# WaeatherNode.net
KiCad netlist of a schematic drawn in EAGLE
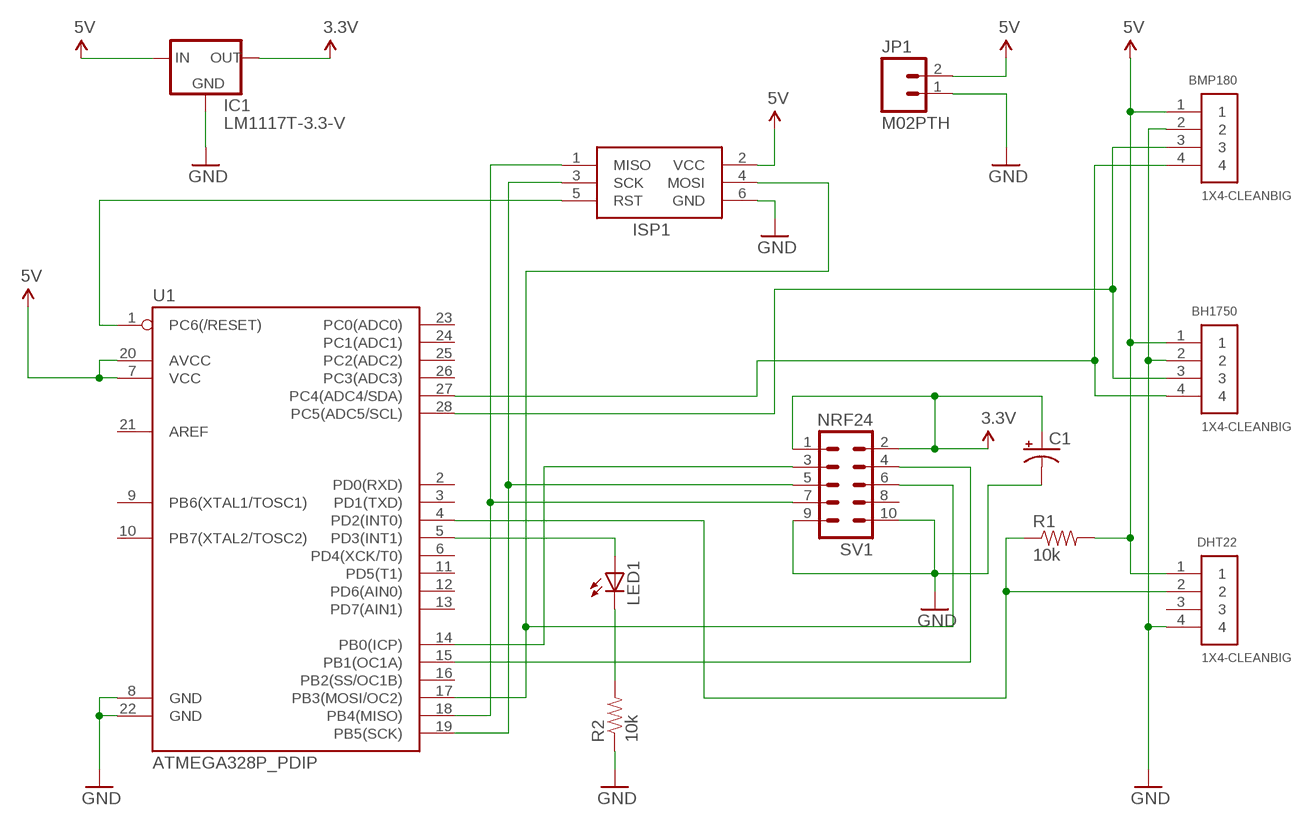
[diagram p0: schematic, sheet 1]

(export (version "E")
  (design (tool "Eeschema 10.0.6"))
  (components
    (comp (ref "BH1750")
      (value "1X4-CLEANBIG")
      (footprint "eagle-import:1X04-CLEANBIG")
      (libsource (lib "eagle-import") (part "1X4-CLEANBIG"))
    )
    (comp (ref "BMP180")
      (value "1X4-CLEANBIG")
      (footprint "eagle-import:1X04-CLEANBIG")
      (libsource (lib "eagle-import") (part "1X4-CLEANBIG"))
    )
    (comp (ref "C1")
      (value "CPOL-USE2.5-7")
      (footprint "eagle-import:E2,5-7")
      (libsource (lib "eagle-import") (part "CPOL-USE2.5-7"))
    )
    (comp (ref "DHT22")
      (value "1X4-CLEANBIG")
      (footprint "eagle-import:1X04-CLEANBIG")
      (libsource (lib "eagle-import") (part "1X4-CLEANBIG"))
    )
    (comp (ref "IC1")
      (value "LM1117T-3.3-V")
      (footprint "eagle-import:TO220V")
      (libsource (lib "eagle-import") (part "LM1117T--V3.3"))
    )
    (comp (ref "ISP1")
      (value "AVRISP-BOX")
      (footprint "eagle-import:AVRISP-BOX")
      (libsource (lib "eagle-import") (part "AVRISP-BOX"))
    )
    (comp (ref "JP1")
      (value "M02PTH")
      (footprint "eagle-import:1X02")
      (libsource (lib "eagle-import") (part "M02PTH"))
    )
    (comp (ref "LED1")
      (value "LED3MM")
      (footprint "eagle-import:LED3MM")
      (libsource (lib "eagle-import") (part "LED3MM"))
    )
    (comp (ref "R1")
      (value "10k")
      (footprint "eagle-import:AXIAL-0.3")
      (libsource (lib "eagle-import") (part "10KOHM-1/4W-1%(PTH)HORIZ"))
    )
    (comp (ref "R2")
      (value "10k")
      (footprint "eagle-import:AXIAL-0.3")
      (libsource (lib "eagle-import") (part "10KOHM-1/4W-1%(PTH)HORIZ"))
    )
    (comp (ref "SV1")
      (value "NRF24")
      (footprint "eagle-import:MA05-2")
      (libsource (lib "eagle-import") (part "MA05-2"))
    )
    (comp (ref "U1")
      (value "ATMEGA328P_PDIP")
      (footprint "eagle-import:DIL28-3")
      (libsource (lib "eagle-import") (part "ATMEGA328P_PDIP"))
    )
  )
  (nets
    (net (code "1") (name "3.3V") (class "Default")
      (node (ref "C1") (pin "+") (pinfunction "+_+") (pintype "passive"))
      (node (ref "IC1") (pin "2") (pinfunction "OUT_2") (pintype "passive"))
      (node (ref "SV1") (pin "1") (pinfunction "1_1") (pintype "passive"))
      (node (ref "SV1") (pin "2") (pinfunction "2_2") (pintype "passive"))
    )
    (net (code "2") (name "5V") (class "Default")
      (node (ref "BH1750") (pin "1") (pinfunction "1_1") (pintype "bidirectional"))
      (node (ref "BMP180") (pin "1") (pinfunction "1_1") (pintype "bidirectional"))
      (node (ref "DHT22") (pin "1") (pinfunction "1_1") (pintype "bidirectional"))
      (node (ref "IC1") (pin "3") (pinfunction "IN_3") (pintype "input"))
      (node (ref "ISP1") (pin "2") (pinfunction "VCC_2") (pintype "power_in"))
      (node (ref "JP1") (pin "2") (pinfunction "2_2") (pintype "passive"))
      (node (ref "R1") (pin "P$2") (pinfunction "2_P$2") (pintype "passive"))
      (node (ref "U1") (pin "20") (pinfunction "AVCC_20") (pintype "bidirectional"))
      (node (ref "U1") (pin "7") (pinfunction "VCC_7") (pintype "bidirectional"))
    )
    (net (code "3") (name "GND") (class "Default")
      (node (ref "BH1750") (pin "2") (pinfunction "2_2") (pintype "bidirectional"))
      (node (ref "BMP180") (pin "2") (pinfunction "2_2") (pintype "bidirectional"))
      (node (ref "C1") (pin "-") (pinfunction "-_-") (pintype "passive"))
      (node (ref "DHT22") (pin "4") (pinfunction "4_4") (pintype "bidirectional"))
      (node (ref "IC1") (pin "1") (pinfunction "GND_1") (pintype "input"))
      (node (ref "ISP1") (pin "6") (pinfunction "GND_6") (pintype "power_in"))
      (node (ref "JP1") (pin "1") (pinfunction "1_1") (pintype "passive"))
      (node (ref "R2") (pin "P$1") (pinfunction "1_P$1") (pintype "passive"))
      (node (ref "SV1") (pin "10") (pinfunction "10_10") (pintype "passive"))
      (node (ref "SV1") (pin "9") (pinfunction "9_9") (pintype "passive"))
      (node (ref "U1") (pin "22") (pinfunction "GND_22") (pintype "bidirectional"))
      (node (ref "U1") (pin "8") (pinfunction "GND_8") (pintype "bidirectional"))
    )
    (net (code "4") (name "Net-(ISP1-MISO)") (class "Default")
      (node (ref "ISP1") (pin "1") (pinfunction "MISO_1") (pintype "input"))
      (node (ref "SV1") (pin "7") (pinfunction "7_7") (pintype "passive"))
      (node (ref "U1") (pin "18") (pinfunction "PB4(MISO)_18") (pintype "bidirectional"))
    )
    (net (code "5") (name "Net-(ISP1-MOSI)") (class "Default")
      (node (ref "ISP1") (pin "4") (pinfunction "MOSI_4") (pintype "output"))
      (node (ref "SV1") (pin "6") (pinfunction "6_6") (pintype "passive"))
      (node (ref "U1") (pin "17") (pinfunction "PB3(MOSI/OC2)_17") (pintype "bidirectional"))
    )
    (net (code "6") (name "Net-(ISP1-RST)") (class "Default")
      (node (ref "ISP1") (pin "5") (pinfunction "RST_5") (pintype "output"))
      (node (ref "U1") (pin "1") (pinfunction "PC6(/RESET)_1") (pintype "bidirectional"))
    )
    (net (code "7") (name "Net-(ISP1-SCK)") (class "Default")
      (node (ref "ISP1") (pin "3") (pinfunction "SCK_3") (pintype "output"))
      (node (ref "SV1") (pin "5") (pinfunction "5_5") (pintype "passive"))
      (node (ref "U1") (pin "19") (pinfunction "PB5(SCK)_19") (pintype "bidirectional"))
    )
    (net (code "8") (name "Net-(LED1-C)") (class "Default")
      (node (ref "LED1") (pin "K") (pinfunction "C_K") (pintype "passive"))
      (node (ref "R2") (pin "P$2") (pinfunction "2_P$2") (pintype "passive"))
    )
    (net (code "9") (name "Net-(R1-1)") (class "Default")
      (node (ref "DHT22") (pin "2") (pinfunction "2_2") (pintype "bidirectional"))
      (node (ref "R1") (pin "P$1") (pinfunction "1_P$1") (pintype "passive"))
      (node (ref "U1") (pin "4") (pinfunction "PD2(INT0)_4") (pintype "bidirectional"))
    )
    (net (code "10") (name "Net-(U1-PB0(ICP))") (class "Default")
      (node (ref "SV1") (pin "3") (pinfunction "3_3") (pintype "passive"))
      (node (ref "U1") (pin "14") (pinfunction "PB0(ICP)_14") (pintype "bidirectional"))
    )
    (net (code "11") (name "Net-(U1-PB1(OC1A))") (class "Default")
      (node (ref "SV1") (pin "4") (pinfunction "4_4") (pintype "passive"))
      (node (ref "U1") (pin "15") (pinfunction "PB1(OC1A)_15") (pintype "bidirectional"))
    )
    (net (code "12") (name "Net-(U1-PC4(ADC4{slash}SDA))") (class "Default")
      (node (ref "BH1750") (pin "4") (pinfunction "4_4") (pintype "bidirectional"))
      (node (ref "BMP180") (pin "4") (pinfunction "4_4") (pintype "bidirectional"))
      (node (ref "U1") (pin "27") (pinfunction "PC4(ADC4/SDA)_27") (pintype "bidirectional"))
    )
    (net (code "13") (name "Net-(U1-PC5(ADC5{slash}SCL))") (class "Default")
      (node (ref "BH1750") (pin "3") (pinfunction "3_3") (pintype "bidirectional"))
      (node (ref "BMP180") (pin "3") (pinfunction "3_3") (pintype "bidirectional"))
      (node (ref "U1") (pin "28") (pinfunction "PC5(ADC5/SCL)_28") (pintype "bidirectional"))
    )
    (net (code "14") (name "Net-(U1-PD3(INT1))") (class "Default")
      (node (ref "LED1") (pin "A") (pinfunction "A_A") (pintype "passive"))
      (node (ref "U1") (pin "5") (pinfunction "PD3(INT1)_5") (pintype "bidirectional"))
    )
    (net (code "15") (name "unconnected-(DHT22-Pad3)") (class "Default")
      (node (ref "DHT22") (pin "3") (pinfunction "3_3") (pintype "bidirectional"))
    )
    (net (code "16") (name "unconnected-(SV1-Pad8)") (class "Default")
      (node (ref "SV1") (pin "8") (pinfunction "8_8") (pintype "passive"))
    )
    (net (code "17") (name "unconnected-(U1-AREF-Pad21)") (class "Default")
      (node (ref "U1") (pin "21") (pinfunction "AREF_21") (pintype "bidirectional"))
    )
    (net (code "18") (name "unconnected-(U1-PB2(SS{slash}OC1B)-Pad16)") (class "Default")
      (node (ref "U1") (pin "16") (pinfunction "PB2(SS/OC1B)_16") (pintype "bidirectional"))
    )
    (net (code "19") (name "unconnected-(U1-PB6(XTAL1{slash}TOSC1)-Pad9)") (class "Default")
      (node (ref "U1") (pin "9") (pinfunction "PB6(XTAL1/TOSC1)_9") (pintype "bidirectional"))
    )
    (net (code "20") (name "unconnected-(U1-PB7(XTAL2{slash}TOSC2)-Pad10)") (class "Default")
      (node (ref "U1") (pin "10") (pinfunction "PB7(XTAL2/TOSC2)_10") (pintype "bidirectional"))
    )
    (net (code "21") (name "unconnected-(U1-PC0(ADC0)-Pad23)") (class "Default")
      (node (ref "U1") (pin "23") (pinfunction "PC0(ADC0)_23") (pintype "bidirectional"))
    )
    (net (code "22") (name "unconnected-(U1-PC1(ADC1)-Pad24)") (class "Default")
      (node (ref "U1") (pin "24") (pinfunction "PC1(ADC1)_24") (pintype "bidirectional"))
    )
    (net (code "23") (name "unconnected-(U1-PC2(ADC2)-Pad25)") (class "Default")
      (node (ref "U1") (pin "25") (pinfunction "PC2(ADC2)_25") (pintype "bidirectional"))
    )
    (net (code "24") (name "unconnected-(U1-PC3(ADC3)-Pad26)") (class "Default")
      (node (ref "U1") (pin "26") (pinfunction "PC3(ADC3)_26") (pintype "bidirectional"))
    )
    (net (code "25") (name "unconnected-(U1-PD0(RXD)-Pad2)") (class "Default")
      (node (ref "U1") (pin "2") (pinfunction "PD0(RXD)_2") (pintype "bidirectional"))
    )
    (net (code "26") (name "unconnected-(U1-PD1(TXD)-Pad3)") (class "Default")
      (node (ref "U1") (pin "3") (pinfunction "PD1(TXD)_3") (pintype "bidirectional"))
    )
    (net (code "27") (name "unconnected-(U1-PD4(XCK{slash}T0)-Pad6)") (class "Default")
      (node (ref "U1") (pin "6") (pinfunction "PD4(XCK/T0)_6") (pintype "bidirectional"))
    )
    (net (code "28") (name "unconnected-(U1-PD5(T1)-Pad11)") (class "Default")
      (node (ref "U1") (pin "11") (pinfunction "PD5(T1)_11") (pintype "bidirectional"))
    )
    (net (code "29") (name "unconnected-(U1-PD6(AIN0)-Pad12)") (class "Default")
      (node (ref "U1") (pin "12") (pinfunction "PD6(AIN0)_12") (pintype "bidirectional"))
    )
    (net (code "30") (name "unconnected-(U1-PD7(AIN1)-Pad13)") (class "Default")
      (node (ref "U1") (pin "13") (pinfunction "PD7(AIN1)_13") (pintype "bidirectional"))
    )
  )
)
